# -Frame.net
KiCad netlist of a schematic drawn in Altium Designer
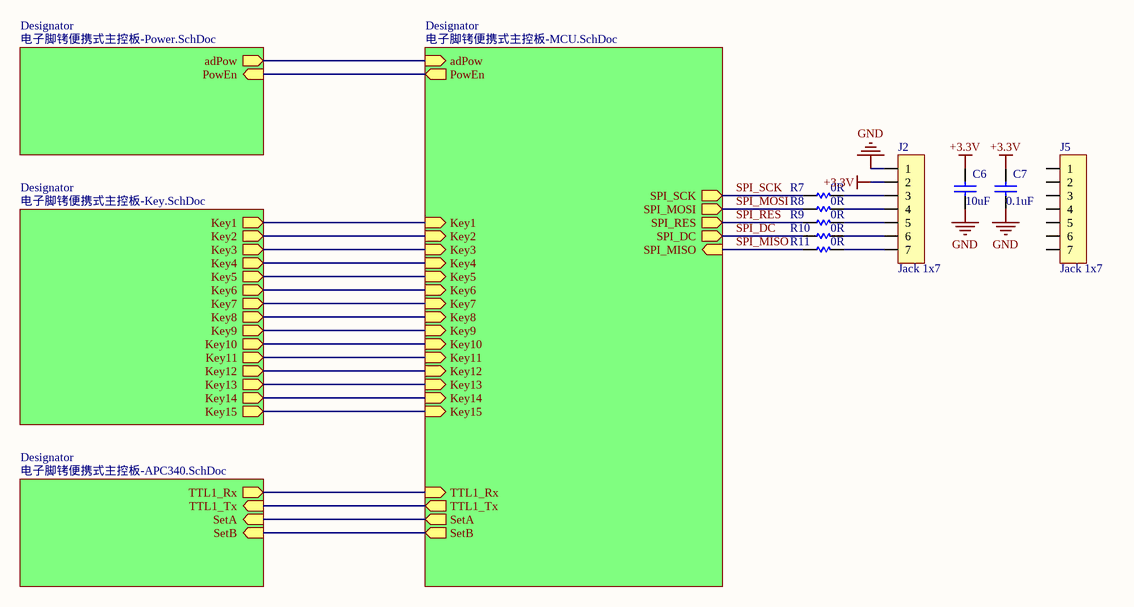
[diagram p0: 电子脚铐便携式主控板-Frame.SchDoc]

(export (version "E")
  (design (tool "Eeschema 10.0.6"))
  (components
    (comp (ref "C6")
      (value "10uF")
      (footprint "C0603")
      (description "CAP")
      (libsource (lib "Passive Components Class") (part "CAP"))
    )
    (comp (ref "C7")
      (value "0.1uF")
      (footprint "C0603")
      (description "CAP")
      (libsource (lib "Passive Components Class") (part "CAP"))
    )
    (comp (ref "J2")
      (value "Jack 1x7")
      (footprint "ZH-7AWD")
      (description "插座")
      (libsource (lib "Connector") (part "Jack 1x7"))
    )
    (comp (ref "J5")
      (value "Jack 1x7")
      (footprint "1.54OLED")
      (description "插座")
      (libsource (lib "Connector") (part "Jack 1x7"))
    )
    (comp (ref "R7") (value "0R") (footprint "R0603") (libsource (lib "RLCYDF") (part "Res")))
    (comp (ref "R8") (value "0R") (footprint "R0603") (libsource (lib "RLCYDF") (part "Res")))
    (comp (ref "R9") (value "0R") (footprint "R0603") (libsource (lib "RLCYDF") (part "Res")))
    (comp (ref "R10") (value "0R") (footprint "R0603") (libsource (lib "RLCYDF") (part "Res")))
    (comp (ref "R11") (value "0R") (footprint "R0603") (libsource (lib "RLCYDF") (part "Res")))
  )
  (nets
    (net (code "1") (name "+3.3V") (class "Default")
      (node (ref "C6") (pin "1") (pinfunction "1_1") (pintype "passive"))
      (node (ref "C7") (pin "1") (pinfunction "1_1") (pintype "passive"))
      (node (ref "J2") (pin "2") (pinfunction "2_2") (pintype "passive"))
    )
    (net (code "18") (name "/SPI_DC") (class "Default")
      (node (ref "R10") (pin "1") (pinfunction "1_1") (pintype "passive"))
    )
    (net (code "19") (name "/SPI_MISO") (class "Default")
      (node (ref "R11") (pin "1") (pinfunction "1_1") (pintype "passive"))
    )
    (net (code "20") (name "/SPI_MOSI") (class "Default")
      (node (ref "R8") (pin "1") (pinfunction "1_1") (pintype "passive"))
    )
    (net (code "21") (name "/SPI_RES") (class "Default")
      (node (ref "R9") (pin "1") (pinfunction "1_1") (pintype "passive"))
    )
    (net (code "22") (name "/SPI_SCK") (class "Default")
      (node (ref "R7") (pin "1") (pinfunction "1_1") (pintype "passive"))
    )
    (net (code "28") (name "GND") (class "Default")
      (node (ref "C6") (pin "2") (pinfunction "2_2") (pintype "passive"))
      (node (ref "C7") (pin "2") (pinfunction "2_2") (pintype "passive"))
      (node (ref "J2") (pin "1") (pinfunction "1_1") (pintype "passive"))
    )
    (net (code "29") (name "Net-(J2-Pad3)") (class "Default")
      (node (ref "J2") (pin "3") (pinfunction "3_3") (pintype "passive"))
      (node (ref "R7") (pin "2") (pinfunction "2_2") (pintype "passive"))
    )
    (net (code "30") (name "Net-(J2-Pad4)") (class "Default")
      (node (ref "J2") (pin "4") (pinfunction "4_4") (pintype "passive"))
      (node (ref "R8") (pin "2") (pinfunction "2_2") (pintype "passive"))
    )
    (net (code "31") (name "Net-(J2-Pad5)") (class "Default")
      (node (ref "J2") (pin "5") (pinfunction "5_5") (pintype "passive"))
      (node (ref "R9") (pin "2") (pinfunction "2_2") (pintype "passive"))
    )
    (net (code "32") (name "Net-(J2-Pad6)") (class "Default")
      (node (ref "J2") (pin "6") (pinfunction "6_6") (pintype "passive"))
      (node (ref "R10") (pin "2") (pinfunction "2_2") (pintype "passive"))
    )
    (net (code "33") (name "Net-(J2-Pad7)") (class "Default")
      (node (ref "J2") (pin "7") (pinfunction "7_7") (pintype "passive"))
      (node (ref "R11") (pin "2") (pinfunction "2_2") (pintype "passive"))
    )
    (net (code "34") (name "unconnected-(J5-Pad1)") (class "Default")
      (node (ref "J5") (pin "1") (pinfunction "1_1") (pintype "passive"))
    )
    (net (code "35") (name "unconnected-(J5-Pad2)") (class "Default")
      (node (ref "J5") (pin "2") (pinfunction "2_2") (pintype "passive"))
    )
    (net (code "36") (name "unconnected-(J5-Pad3)") (class "Default")
      (node (ref "J5") (pin "3") (pinfunction "3_3") (pintype "passive"))
    )
    (net (code "37") (name "unconnected-(J5-Pad4)") (class "Default")
      (node (ref "J5") (pin "4") (pinfunction "4_4") (pintype "passive"))
    )
    (net (code "38") (name "unconnected-(J5-Pad5)") (class "Default")
      (node (ref "J5") (pin "5") (pinfunction "5_5") (pintype "passive"))
    )
    (net (code "39") (name "unconnected-(J5-Pad6)") (class "Default")
      (node (ref "J5") (pin "6") (pinfunction "6_6") (pintype "passive"))
    )
    (net (code "40") (name "unconnected-(J5-Pad7)") (class "Default")
      (node (ref "J5") (pin "7") (pinfunction "7_7") (pintype "passive"))
    )
  )
)
